# ROm-el_HN61256_Adapter.net
KiCad netlist of a schematic drawn in EAGLE
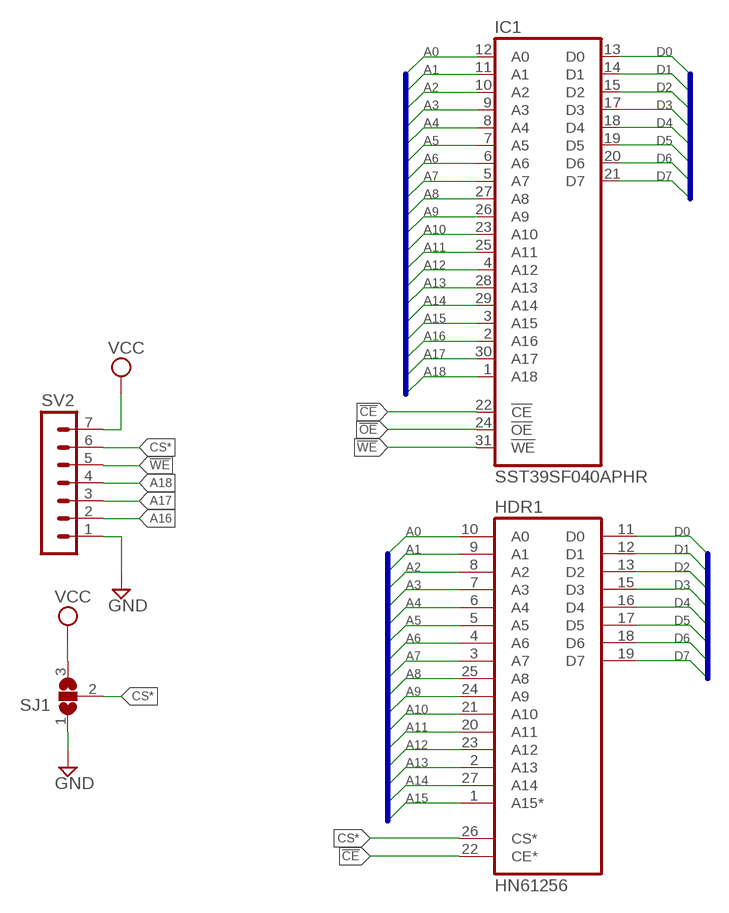
[diagram p0: schematic, sheet 1]

(export (version "E")
  (design (tool "Eeschema 10.0.6"))
  (components
    (comp (ref "HDR1")
      (value "HN61256")
      (footprint "eagle-import:DIL28-6")
      (libsource (lib "eagle-import") (part "HN61256"))
    )
    (comp (ref "IC1")
      (value "SST39SF040APHR")
      (footprint "eagle-import:DIL32-RP")
      (libsource (lib "eagle-import") (part "SST39SF040APHR"))
    )
    (comp (ref "SJ1")
      (value "SJ2W")
      (footprint "eagle-import:SJ_2")
      (libsource (lib "eagle-import") (part "SJ2W"))
    )
    (comp (ref "SV2")
      (value "MA07-1")
      (footprint "eagle-import:MA07-1")
      (libsource (lib "eagle-import") (part "MA07-1"))
    )
  )
  (nets
    (net (code "1") (name "/A0") (class "Default")
      (node (ref "HDR1") (pin "10") (pinfunction "A0_10") (pintype "input"))
      (node (ref "IC1") (pin "12") (pinfunction "A0_12") (pintype "input"))
    )
    (net (code "2") (name "/A1") (class "Default")
      (node (ref "HDR1") (pin "9") (pinfunction "A1_9") (pintype "input"))
      (node (ref "IC1") (pin "11") (pinfunction "A1_11") (pintype "input"))
    )
    (net (code "3") (name "/A2") (class "Default")
      (node (ref "HDR1") (pin "8") (pinfunction "A2_8") (pintype "input"))
      (node (ref "IC1") (pin "10") (pinfunction "A2_10") (pintype "input"))
    )
    (net (code "4") (name "/A3") (class "Default")
      (node (ref "HDR1") (pin "7") (pinfunction "A3_7") (pintype "input"))
      (node (ref "IC1") (pin "9") (pinfunction "A3_9") (pintype "input"))
    )
    (net (code "5") (name "/A4") (class "Default")
      (node (ref "HDR1") (pin "6") (pinfunction "A4_6") (pintype "input"))
      (node (ref "IC1") (pin "8") (pinfunction "A4_8") (pintype "input"))
    )
    (net (code "6") (name "/A5") (class "Default")
      (node (ref "HDR1") (pin "5") (pinfunction "A5_5") (pintype "input"))
      (node (ref "IC1") (pin "7") (pinfunction "A5_7") (pintype "input"))
    )
    (net (code "7") (name "/A6") (class "Default")
      (node (ref "HDR1") (pin "4") (pinfunction "A6_4") (pintype "input"))
      (node (ref "IC1") (pin "6") (pinfunction "A6_6") (pintype "input"))
    )
    (net (code "8") (name "/A7") (class "Default")
      (node (ref "HDR1") (pin "3") (pinfunction "A7_3") (pintype "input"))
      (node (ref "IC1") (pin "5") (pinfunction "A7_5") (pintype "input"))
    )
    (net (code "9") (name "/A8") (class "Default")
      (node (ref "HDR1") (pin "25") (pinfunction "A8_25") (pintype "input"))
      (node (ref "IC1") (pin "27") (pinfunction "A8_27") (pintype "input"))
    )
    (net (code "10") (name "/A9") (class "Default")
      (node (ref "HDR1") (pin "24") (pinfunction "A9_24") (pintype "input"))
      (node (ref "IC1") (pin "26") (pinfunction "A9_26") (pintype "input"))
    )
    (net (code "11") (name "/A10") (class "Default")
      (node (ref "HDR1") (pin "21") (pinfunction "A10_21") (pintype "input"))
      (node (ref "IC1") (pin "23") (pinfunction "A10_23") (pintype "input"))
    )
    (net (code "12") (name "/A11") (class "Default")
      (node (ref "HDR1") (pin "20") (pinfunction "A11_20") (pintype "input"))
      (node (ref "IC1") (pin "25") (pinfunction "A11_25") (pintype "input"))
    )
    (net (code "13") (name "/A12") (class "Default")
      (node (ref "HDR1") (pin "23") (pinfunction "A12_23") (pintype "input"))
      (node (ref "IC1") (pin "4") (pinfunction "A12_4") (pintype "input"))
    )
    (net (code "14") (name "/A13") (class "Default")
      (node (ref "HDR1") (pin "2") (pinfunction "A13_2") (pintype "input"))
      (node (ref "IC1") (pin "28") (pinfunction "A13_28") (pintype "input"))
    )
    (net (code "15") (name "/A14") (class "Default")
      (node (ref "HDR1") (pin "27") (pinfunction "A14_27") (pintype "input"))
      (node (ref "IC1") (pin "29") (pinfunction "A14_29") (pintype "input"))
    )
    (net (code "16") (name "/A15") (class "Default")
      (node (ref "HDR1") (pin "1") (pinfunction "A15*_1") (pintype "input"))
      (node (ref "IC1") (pin "3") (pinfunction "A15_3") (pintype "input"))
    )
    (net (code "17") (name "/D0") (class "Default")
      (node (ref "HDR1") (pin "11") (pinfunction "D0_11") (pintype "bidirectional"))
      (node (ref "IC1") (pin "13") (pinfunction "D0_13") (pintype "bidirectional"))
    )
    (net (code "18") (name "/D1") (class "Default")
      (node (ref "HDR1") (pin "12") (pinfunction "D1_12") (pintype "bidirectional"))
      (node (ref "IC1") (pin "14") (pinfunction "D1_14") (pintype "bidirectional"))
    )
    (net (code "19") (name "/D2") (class "Default")
      (node (ref "HDR1") (pin "13") (pinfunction "D2_13") (pintype "bidirectional"))
      (node (ref "IC1") (pin "15") (pinfunction "D2_15") (pintype "bidirectional"))
    )
    (net (code "20") (name "/D3") (class "Default")
      (node (ref "HDR1") (pin "15") (pinfunction "D3_15") (pintype "bidirectional"))
      (node (ref "IC1") (pin "17") (pinfunction "D3_17") (pintype "bidirectional"))
    )
    (net (code "21") (name "/D4") (class "Default")
      (node (ref "HDR1") (pin "16") (pinfunction "D4_16") (pintype "bidirectional"))
      (node (ref "IC1") (pin "18") (pinfunction "D4_18") (pintype "bidirectional"))
    )
    (net (code "22") (name "/D5") (class "Default")
      (node (ref "HDR1") (pin "17") (pinfunction "D5_17") (pintype "bidirectional"))
      (node (ref "IC1") (pin "19") (pinfunction "D5_19") (pintype "bidirectional"))
    )
    (net (code "23") (name "/D6") (class "Default")
      (node (ref "HDR1") (pin "18") (pinfunction "D6_18") (pintype "bidirectional"))
      (node (ref "IC1") (pin "20") (pinfunction "D6_20") (pintype "bidirectional"))
    )
    (net (code "24") (name "/D7") (class "Default")
      (node (ref "HDR1") (pin "19") (pinfunction "D7_19") (pintype "bidirectional"))
      (node (ref "IC1") (pin "21") (pinfunction "D7_21") (pintype "bidirectional"))
    )
    (net (code "25") (name "/~{CE}") (class "Default")
      (node (ref "HDR1") (pin "22") (pinfunction "CE*_22") (pintype "input"))
      (node (ref "IC1") (pin "22") (pinfunction "~{CE}_22") (pintype "input"))
    )
    (net (code "26") (name "/~{OE}") (class "Default")
      (node (ref "IC1") (pin "24") (pinfunction "~{OE}_24") (pintype "input"))
    )
    (net (code "27") (name "/~{WE}") (class "Default")
      (node (ref "IC1") (pin "31") (pinfunction "~{WE}_31") (pintype "input"))
      (node (ref "SV2") (pin "5") (pinfunction "5_5") (pintype "passive"))
    )
    (net (code "28") (name "A16") (class "Default")
      (node (ref "IC1") (pin "2") (pinfunction "A16_2") (pintype "input"))
      (node (ref "SV2") (pin "2") (pinfunction "2_2") (pintype "passive"))
    )
    (net (code "29") (name "A17") (class "Default")
      (node (ref "IC1") (pin "30") (pinfunction "A17_30") (pintype "input"))
      (node (ref "SV2") (pin "3") (pinfunction "3_3") (pintype "passive"))
    )
    (net (code "30") (name "A18") (class "Default")
      (node (ref "IC1") (pin "1") (pinfunction "A18_1") (pintype "input"))
      (node (ref "SV2") (pin "4") (pinfunction "4_4") (pintype "passive"))
    )
    (net (code "31") (name "CS*") (class "Default")
      (node (ref "HDR1") (pin "26") (pinfunction "CS*_26") (pintype "input"))
      (node (ref "SJ1") (pin "2") (pinfunction "2_2") (pintype "passive"))
      (node (ref "SV2") (pin "6") (pinfunction "6_6") (pintype "passive"))
    )
    (net (code "32") (name "GND") (class "Default")
      (node (ref "SJ1") (pin "1") (pinfunction "1_1") (pintype "passive"))
      (node (ref "SV2") (pin "1") (pinfunction "1_1") (pintype "passive"))
    )
    (net (code "33") (name "VCC") (class "Default")
      (node (ref "SJ1") (pin "3") (pinfunction "3_3") (pintype "passive"))
      (node (ref "SV2") (pin "7") (pinfunction "7_7") (pintype "passive"))
    )
  )
)
